# emojinecklace.net
KiCad netlist of a schematic drawn in EAGLE
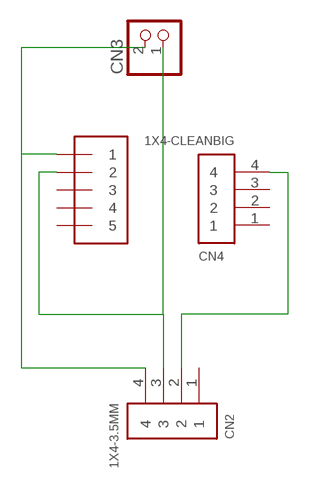
[diagram p0: schematic, sheet 1]

(export (version "E")
  (design (tool "Eeschema 10.0.6"))
  (components
    (comp (ref "CN2")
      (value "1X4-3.5MM")
      (footprint "eagle-import:1X04-3.5MM")
      (libsource (lib "eagle-import") (part "1X4-3.5MM"))
    )
    (comp (ref "CN3")
      (value "JST_2PIN-THM")
      (footprint "eagle-import:JST-PH-2-THM")
      (libsource (lib "eagle-import") (part "JST_2PIN-THM"))
    )
    (comp (ref "CN4")
      (value "1X4-CLEANBIG")
      (footprint "eagle-import:1X04-CLEANBIG")
      (libsource (lib "eagle-import") (part "1X4-CLEANBIG"))
    )
    (comp (ref "J1")
      (value "1X5")
      (footprint "eagle-import:1X05-3.5MM")
      (libsource (lib "eagle-import") (part "1X5"))
    )
  )
  (nets
    (net (code "1") (name "Net-(CN2-Pad2)") (class "Default")
      (node (ref "CN2") (pin "2") (pinfunction "2_2") (pintype "bidirectional"))
      (node (ref "CN4") (pin "4") (pinfunction "4_4") (pintype "bidirectional"))
    )
    (net (code "2") (name "Net-(CN3-1)") (class "Default")
      (node (ref "CN2") (pin "4") (pinfunction "4_4") (pintype "bidirectional"))
      (node (ref "CN3") (pin "2") (pinfunction "1_2") (pintype "passive"))
      (node (ref "J1") (pin "1") (pinfunction "1_1") (pintype "passive"))
    )
    (net (code "3") (name "Net-(CN3-2)") (class "Default")
      (node (ref "CN2") (pin "3") (pinfunction "3_3") (pintype "bidirectional"))
      (node (ref "CN3") (pin "1") (pinfunction "2_1") (pintype "passive"))
      (node (ref "J1") (pin "2") (pinfunction "2_2") (pintype "passive"))
    )
    (net (code "4") (name "unconnected-(CN2-Pad1)") (class "Default")
      (node (ref "CN2") (pin "1") (pinfunction "1_1") (pintype "bidirectional"))
    )
    (net (code "5") (name "unconnected-(CN4-Pad1)") (class "Default")
      (node (ref "CN4") (pin "1") (pinfunction "1_1") (pintype "bidirectional"))
    )
    (net (code "6") (name "unconnected-(CN4-Pad2)") (class "Default")
      (node (ref "CN4") (pin "2") (pinfunction "2_2") (pintype "bidirectional"))
    )
    (net (code "7") (name "unconnected-(CN4-Pad3)") (class "Default")
      (node (ref "CN4") (pin "3") (pinfunction "3_3") (pintype "bidirectional"))
    )
    (net (code "8") (name "unconnected-(J1-Pad3)") (class "Default")
      (node (ref "J1") (pin "3") (pinfunction "3_3") (pintype "passive"))
    )
    (net (code "9") (name "unconnected-(J1-Pad4)") (class "Default")
      (node (ref "J1") (pin "4") (pinfunction "4_4") (pintype "passive"))
    )
    (net (code "10") (name "unconnected-(J1-Pad5)") (class "Default")
      (node (ref "J1") (pin "5") (pinfunction "5_5") (pintype "passive"))
    )
  )
)
